# Cas_1.net
KiCad netlist of a schematic drawn in Altium Designer
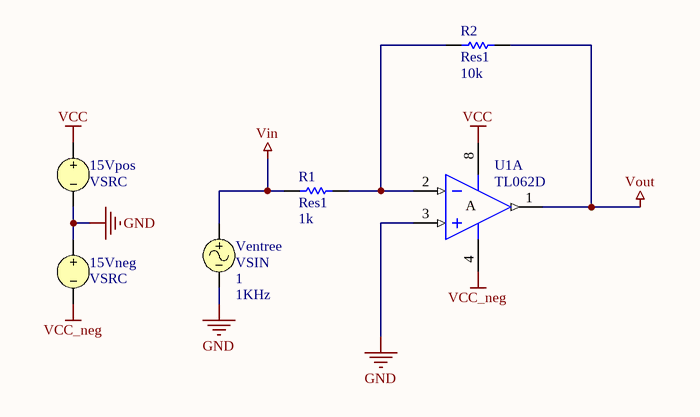
[diagram p0: Cas_1.SchDoc]

(export (version "E")
  (design (tool "Eeschema 10.0.6"))
  (components
    (comp (ref "15Vneg")
      (value "VSRC")
      (description "Voltage Source")
      (fields (field (name "PUBLISHER") "Altium Limited"))
      (libsource (lib "Simulation Generic Components") (part "VSRC"))
    )
    (comp (ref "15Vpos")
      (value "VSRC")
      (description "Voltage Source")
      (fields (field (name "PUBLISHER") "Altium Limited"))
      (libsource (lib "Simulation Generic Components") (part "VSRC"))
    )
    (comp (ref "R1")
      (value "Res1")
      (footprint "AXIAL-0.3")
      (description "Resistor")
      (fields (field (name "ALTIUM_VALUE") "1k") (field (name "PUBLISHER") "Altium Limited"))
      (libsource (lib "Miscellaneous Devices") (part "Res1"))
    )
    (comp (ref "R2")
      (value "Res1")
      (footprint "AXIAL-0.3")
      (description "Resistor")
      (fields (field (name "ALTIUM_VALUE") "10k") (field (name "PUBLISHER") "Altium Limited"))
      (libsource (lib "Miscellaneous Devices") (part "Res1"))
    )
    (comp (ref "U1")
      (value "TL062D")
      (footprint "D008_L")
      (description "Low-Power JFET-Input Operational Amplifier")
      (fields (field (name "PUBLISHER") "Altium Limited"))
      (libsource (lib "TI Operational Amplifier") (part "TL062D"))
    )
    (comp (ref "Ventree")
      (value "VSIN")
      (description "Sinusoidal Voltage Source")
      (fields
        (field (name "AMPLITUDE") "1")
        (field (name "FREQUENCY") "1KHz")
        (field (name "PUBLISHER") "Altium Limited")
      )
      (libsource (lib "Simulation Sources") (part "VSIN"))
    )
  )
  (nets
    (net (code "1") (name "GND") (class "Default")
      (node (ref "15Vneg") (pin "1") (pinfunction "1_1") (pintype "passive"))
      (node (ref "15Vpos") (pin "2") (pinfunction "2_2") (pintype "passive"))
      (node (ref "U1") (pin "3") (pinfunction "IN+_3") (pintype "input"))
      (node (ref "Ventree") (pin "2") (pinfunction "2_2") (pintype "passive"))
    )
    (net (code "2") (name "Net-(U1A-IN-)") (class "Default")
      (node (ref "R1") (pin "2") (pinfunction "2_2") (pintype "passive"))
      (node (ref "R2") (pin "1") (pinfunction "1_1") (pintype "passive"))
      (node (ref "U1") (pin "2") (pinfunction "IN-_2") (pintype "input"))
    )
    (net (code "3") (name "VCC") (class "Default")
      (node (ref "15Vpos") (pin "1") (pinfunction "1_1") (pintype "passive"))
      (node (ref "U1") (pin "8") (pinfunction "V+_8") (pintype "power_in"))
    )
    (net (code "4") (name "VCC_neg") (class "Default")
      (node (ref "15Vneg") (pin "2") (pinfunction "2_2") (pintype "passive"))
      (node (ref "U1") (pin "4") (pinfunction "V-_4") (pintype "power_in"))
    )
    (net (code "5") (name "Vin") (class "Default")
      (node (ref "R1") (pin "1") (pinfunction "1_1") (pintype "passive"))
      (node (ref "Ventree") (pin "1") (pinfunction "1_1") (pintype "passive"))
    )
    (net (code "6") (name "Vout") (class "Default")
      (node (ref "R2") (pin "2") (pinfunction "2_2") (pintype "passive"))
      (node (ref "U1") (pin "1") (pinfunction "OUT_1") (pintype "output"))
    )
  )
)
